# Buck_eFuse.net
KiCad netlist of a schematic drawn in EAGLE
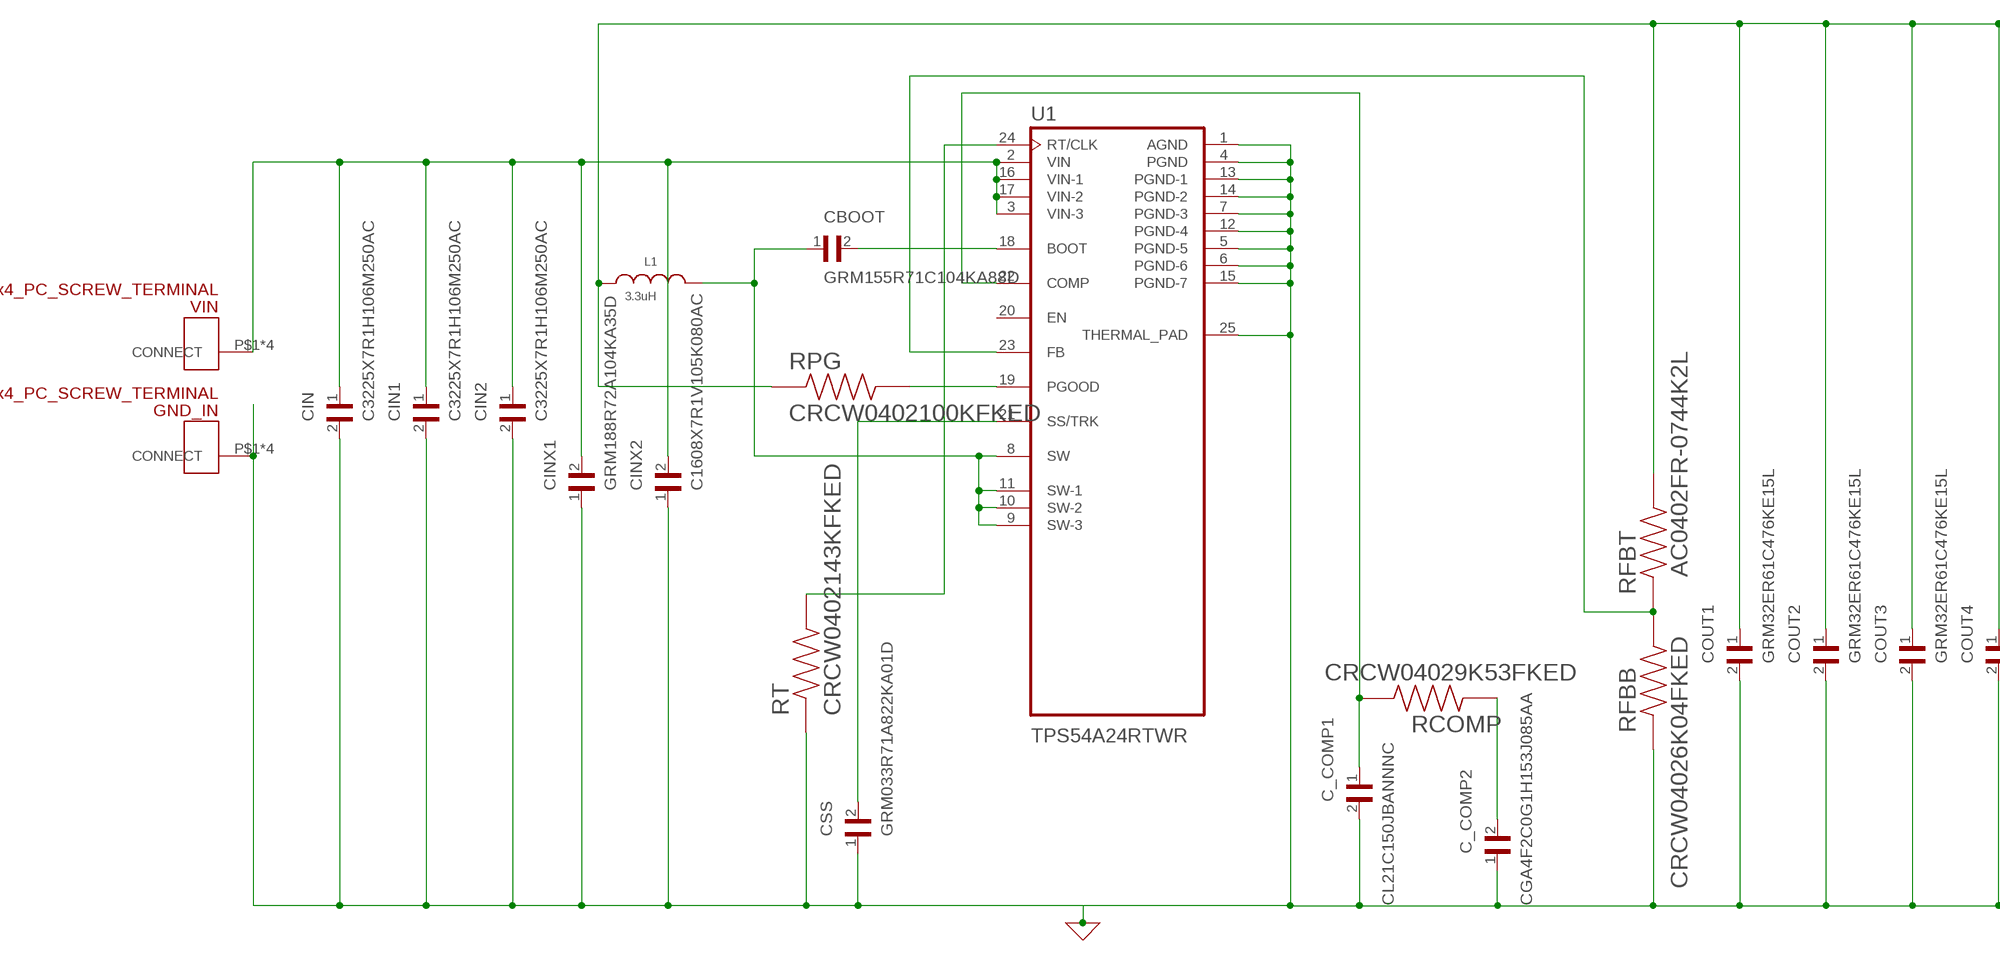
[diagram p0: schematic, sheet 1, part 1 of 2]
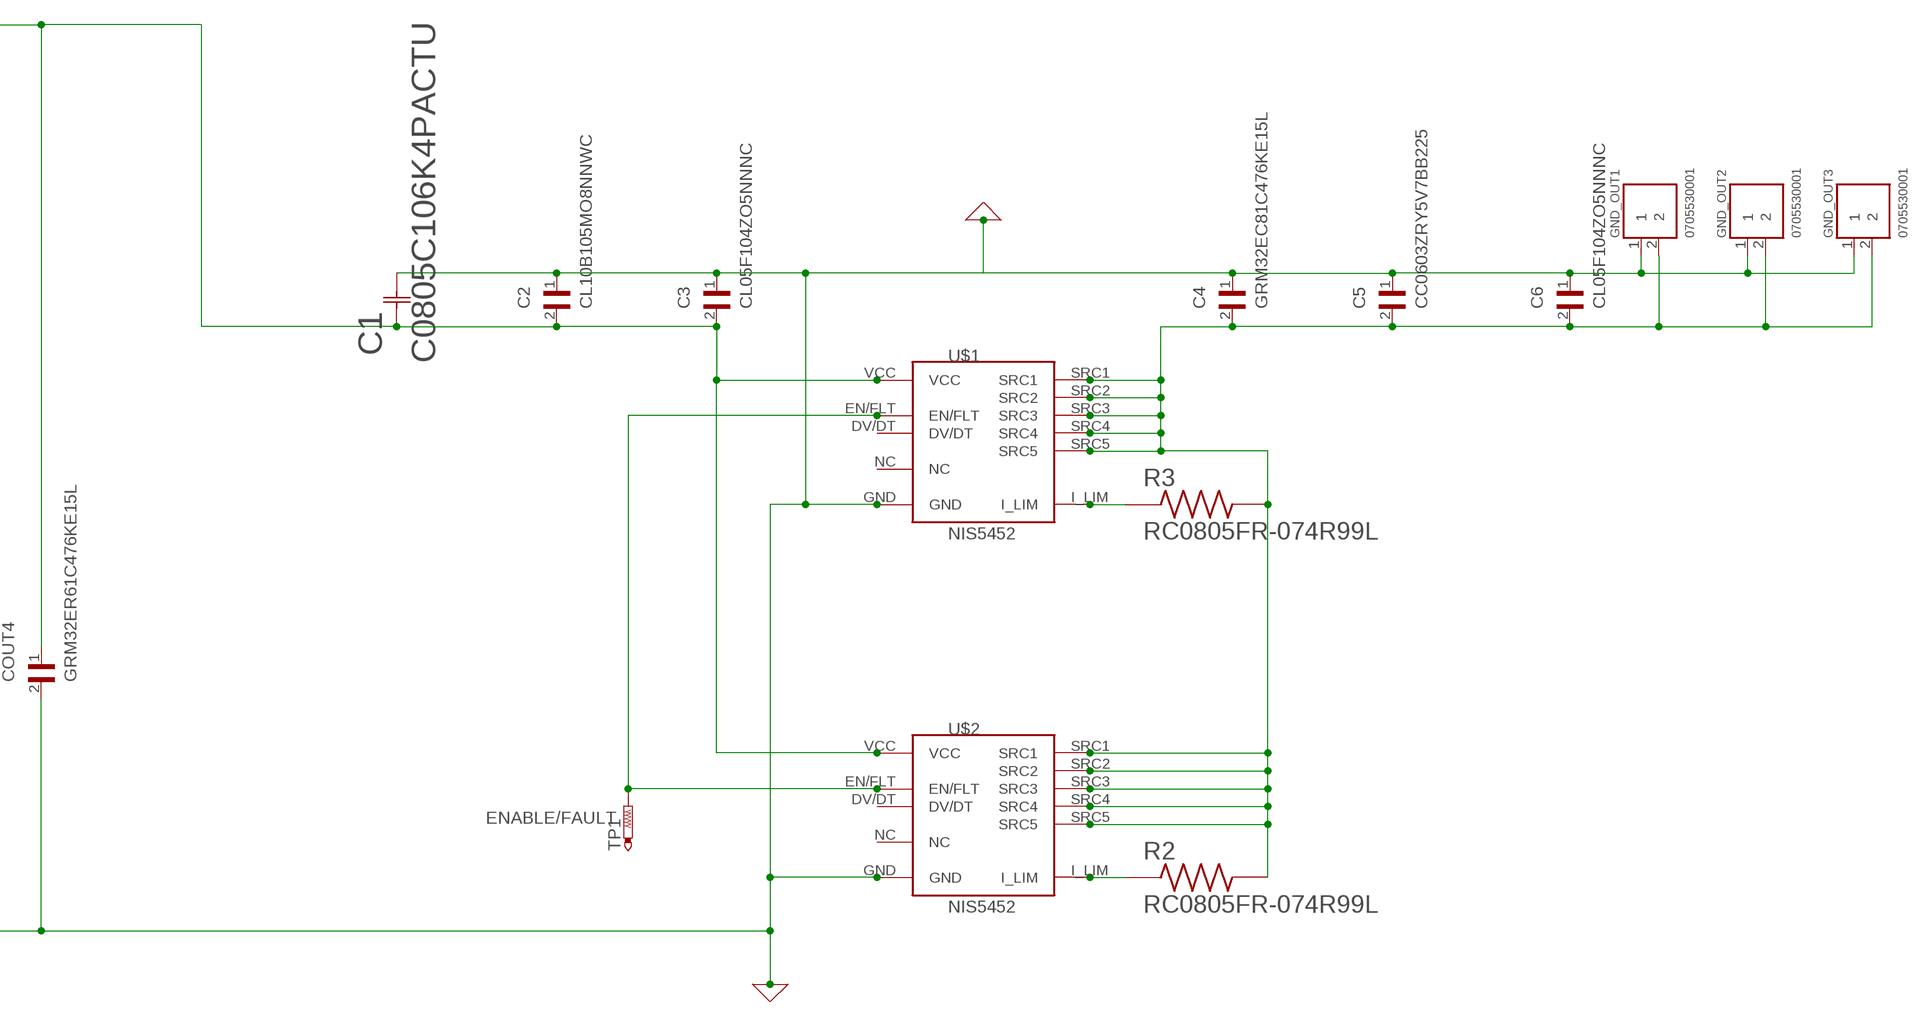
[diagram p1: schematic, sheet 1, part 2 of 2]

(export (version "E")
  (design (tool "Eeschema 10.0.6"))
  (components
    (comp (ref "C1")
      (value "C0805C106K4PACTU")
      (footprint "eagle-import:CAP_C0805")
      (libsource (lib "eagle-import") (part "C0805C106K4PACTU"))
    )
    (comp (ref "C2")
      (value "CL10B105MO8NNWC")
      (footprint "eagle-import:CAPC1608X90N")
      (fields
        (field (name "DIGI-KEY_PART_NUMBER") "1276-6524-1-ND")
        (field (name "MF") "Samsung Electro-Mechanics")
      )
      (libsource (lib "eagle-import") (part "CL10B105MO8NNWC"))
    )
    (comp (ref "C3")
      (value "CL05F104ZO5NNNC")
      (footprint "eagle-import:CAPC1005X55N")
      (fields
        (field (name "DIGI-KEY_PART_NUMBER") "1276-1004-1-ND")
        (field (name "MF") "Samsung Electro-Mechanics")
      )
      (libsource (lib "eagle-import") (part "CL05F104ZO5NNNC"))
    )
    (comp (ref "C4")
      (value "GRM32EC81C476KE15L")
      (footprint "eagle-import:CAPC3225X270N")
      (fields (field (name "DIGI-KEY_PART_NUMBER") "490-10531-1-ND") (field (name "MF") "Murata Electronics"))
      (libsource (lib "eagle-import") (part "GRM32EC81C476KE15L"))
    )
    (comp (ref "C5")
      (value "CC0603ZRY5V7BB225")
      (footprint "eagle-import:CAPC1608X90")
      (fields (field (name "DIGI-KEY_PART_NUMBER") "311-3416-1-ND") (field (name "MF") "Yageo"))
      (libsource (lib "eagle-import") (part "CC0603ZRY5V7BB225"))
    )
    (comp (ref "C6")
      (value "CL05F104ZO5NNNC")
      (footprint "eagle-import:CAPC1005X55N")
      (fields
        (field (name "DIGI-KEY_PART_NUMBER") "1276-1004-1-ND")
        (field (name "MF") "Samsung Electro-Mechanics")
      )
      (libsource (lib "eagle-import") (part "CL05F104ZO5NNNC"))
    )
    (comp (ref "CBOOT")
      (value "GRM155R71C104KA88D")
      (footprint "eagle-import:CAPC1005X55N")
      (fields (field (name "MF") "Murata"))
      (libsource (lib "eagle-import") (part "GRM155R71C104KA88D"))
    )
    (comp (ref "CIN")
      (value "C3225X7R1H106M250AC")
      (footprint "eagle-import:CAPC3225X280N")
      (fields (field (name "DIGI-KEY_PART_NUMBER") "445-14933-1-ND") (field (name "MF") "TDK"))
      (libsource (lib "eagle-import") (part "C3225X7R1H106M250AC"))
    )
    (comp (ref "CIN1")
      (value "C3225X7R1H106M250AC")
      (footprint "eagle-import:CAPC3225X280N")
      (fields (field (name "DIGI-KEY_PART_NUMBER") "445-14933-1-ND") (field (name "MF") "TDK"))
      (libsource (lib "eagle-import") (part "C3225X7R1H106M250AC"))
    )
    (comp (ref "CIN2")
      (value "C3225X7R1H106M250AC")
      (footprint "eagle-import:CAPC3225X280N")
      (fields (field (name "DIGI-KEY_PART_NUMBER") "445-14933-1-ND") (field (name "MF") "TDK"))
      (libsource (lib "eagle-import") (part "C3225X7R1H106M250AC"))
    )
    (comp (ref "CINX1")
      (value "GRM188R72A104KA35D")
      (footprint "eagle-import:CAPC1608X90N")
      (fields (field (name "MF") "Murata Electronics"))
      (libsource (lib "eagle-import") (part "GRM188R72A104KA35D"))
    )
    (comp (ref "CINX2")
      (value "C1608X7R1V105K080AC")
      (footprint "eagle-import:CAPC1608X90N")
      (fields (field (name "MF") "TDK"))
      (libsource (lib "eagle-import") (part "C1608X7R1V105K080AC"))
    )
    (comp (ref "COUT1")
      (value "GRM32ER61C476KE15L")
      (footprint "eagle-import:CAPC3225X270N")
      (fields (field (name "MF") "Murata Electronics"))
      (libsource (lib "eagle-import") (part "GRM32ER61C476KE15L"))
    )
    (comp (ref "COUT2")
      (value "GRM32ER61C476KE15L")
      (footprint "eagle-import:CAPC3225X270N")
      (fields (field (name "MF") "Murata Electronics"))
      (libsource (lib "eagle-import") (part "GRM32ER61C476KE15L"))
    )
    (comp (ref "COUT3")
      (value "GRM32ER61C476KE15L")
      (footprint "eagle-import:CAPC3225X270N")
      (fields (field (name "MF") "Murata Electronics"))
      (libsource (lib "eagle-import") (part "GRM32ER61C476KE15L"))
    )
    (comp (ref "COUT4")
      (value "GRM32ER61C476KE15L")
      (footprint "eagle-import:CAPC3225X270N")
      (fields (field (name "MF") "Murata Electronics"))
      (libsource (lib "eagle-import") (part "GRM32ER61C476KE15L"))
    )
    (comp (ref "CSS")
      (value "GRM033R71A822KA01D")
      (footprint "eagle-import:CAPC0603X33N")
      (fields (field (name "MF") "Murata Electronics"))
      (libsource (lib "eagle-import") (part "GRM033R71A822KA01D"))
    )
    (comp (ref "C_COMP1")
      (value "CL21C150JBANNNC")
      (footprint "eagle-import:CAPC2012X140N")
      (fields (field (name "MF") "Samsung"))
      (libsource (lib "eagle-import") (part "CL21C150JBANNNC"))
    )
    (comp (ref "C_COMP2")
      (value "CGA4F2C0G1H153J085AA")
      (footprint "eagle-import:CAPC2012X100N")
      (fields (field (name "MF") "TDK"))
      (libsource (lib "eagle-import") (part "CGA4F2C0G1H153J085AA"))
    )
    (comp (ref "GND_IN")
      (value "2X2_PC_SCREW_TERMINAL")
      (footprint "eagle-import:SCREW_TERMINAL")
      (libsource (lib "eagle-import") (part "2X2_PC_SCREW_TERMINAL"))
    )
    (comp (ref "GND_OUT1")
      (value "0705530001")
      (footprint "eagle-import:MOLEX_0705530001")
      (fields (field (name "DIGI-KEY_PART_NUMBER") "WM4900-ND") (field (name "MF") "Molex"))
      (libsource (lib "eagle-import") (part "0705530001"))
    )
    (comp (ref "GND_OUT2")
      (value "0705530001")
      (footprint "eagle-import:MOLEX_0705530001")
      (fields (field (name "DIGI-KEY_PART_NUMBER") "WM4900-ND") (field (name "MF") "Molex"))
      (libsource (lib "eagle-import") (part "0705530001"))
    )
    (comp (ref "GND_OUT3")
      (value "0705530001")
      (footprint "eagle-import:MOLEX_0705530001")
      (fields (field (name "DIGI-KEY_PART_NUMBER") "WM4900-ND") (field (name "MF") "Molex"))
      (libsource (lib "eagle-import") (part "0705530001"))
    )
    (comp (ref "L1")
      (value "3.3uH")
      (footprint "eagle-import:WE-HCC_1090")
      (libsource (lib "eagle-import") (part "WE-HCC_1090_7443330330"))
    )
    (comp (ref "R2")
      (value "RC0805FR-074R99L")
      (footprint "eagle-import:RESC2012X60N")
      (fields (field (name "DIGI-KEY_PART_NUMBER") "311-4.99CRCT-ND") (field (name "MF") "Yageo"))
      (libsource (lib "eagle-import") (part "RC0805FR-074R99L"))
    )
    (comp (ref "R3")
      (value "RC0805FR-074R99L")
      (footprint "eagle-import:RESC2012X60N")
      (fields (field (name "DIGI-KEY_PART_NUMBER") "311-4.99CRCT-ND") (field (name "MF") "Yageo"))
      (libsource (lib "eagle-import") (part "RC0805FR-074R99L"))
    )
    (comp (ref "RCOMP")
      (value "CRCW04029K53FKED")
      (footprint "eagle-import:RESC1005X40N")
      (fields (field (name "MF") "Vishay"))
      (libsource (lib "eagle-import") (part "CRCW04029K53FKED"))
    )
    (comp (ref "RFBB")
      (value "CRCW04026K04FKED")
      (footprint "eagle-import:RESC1005X40N")
      (fields (field (name "MF") "Vishay Dale"))
      (libsource (lib "eagle-import") (part "CRCW04026K04FKED"))
    )
    (comp (ref "RFBT")
      (value "AC0402FR-0744K2L")
      (footprint "eagle-import:RESC1005X37N")
      (fields (field (name "MF") "Yageo"))
      (libsource (lib "eagle-import") (part "AC0402FR-0744K2L"))
    )
    (comp (ref "RPG")
      (value "CRCW0402100KFKED")
      (footprint "eagle-import:RESC1005X40N")
      (fields (field (name "MF") "Vishay"))
      (libsource (lib "eagle-import") (part "CRCW0402100KFKED"))
    )
    (comp (ref "RT")
      (value "CRCW0402143KFKED")
      (footprint "eagle-import:RESC1005X40N")
      (fields (field (name "MF") "Vishay"))
      (libsource (lib "eagle-import") (part "CRCW0402143KFKED"))
    )
    (comp (ref "TP1")
      (value "PTR1B2,54")
      (footprint "eagle-import:B2,54")
      (libsource (lib "eagle-import") (part "PTR1B2,54"))
    )
    (comp (ref "U$1")
      (value "NIS5452")
      (footprint "eagle-import:WDFN10")
      (libsource (lib "eagle-import") (part "NIS5452"))
    )
    (comp (ref "U$2")
      (value "NIS5452")
      (footprint "eagle-import:WDFN10")
      (libsource (lib "eagle-import") (part "NIS5452"))
    )
    (comp (ref "U1")
      (value "TPS54A24RTWR")
      (footprint "eagle-import:VQFN50P400X400X100-24N")
      (fields (field (name "MF") "Texas Instruments"))
      (libsource (lib "eagle-import") (part "TPS54A24RTWR"))
    )
    (comp (ref "VIN")
      (value "2X2_PC_SCREW_TERMINAL")
      (footprint "eagle-import:SCREW_TERMINAL")
      (libsource (lib "eagle-import") (part "2X2_PC_SCREW_TERMINAL"))
    )
  )
  (nets
    (net (code "1") (name "/ENABLE{slash}FAULT") (class "Default")
      (node (ref "TP1") (pin "TP") (pinfunction "TP_TP") (pintype "input"))
      (node (ref "U$1") (pin "EN/FLT") (pinfunction "EN/FLT_EN/FLT") (pintype "bidirectional"))
      (node (ref "U$2") (pin "EN/FLT") (pinfunction "EN/FLT_EN/FLT") (pintype "bidirectional"))
    )
    (net (code "2") (name "GND") (class "Default")
      (node (ref "C1") (pin "2") (pinfunction "2_2") (pintype "passive"))
      (node (ref "C2") (pin "1") (pinfunction "1_1") (pintype "passive"))
      (node (ref "C3") (pin "1") (pinfunction "1_1") (pintype "passive"))
      (node (ref "C4") (pin "1") (pinfunction "1_1") (pintype "passive"))
      (node (ref "C5") (pin "1") (pinfunction "1_1") (pintype "passive"))
      (node (ref "C6") (pin "1") (pinfunction "1_1") (pintype "passive"))
      (node (ref "CIN") (pin "2") (pinfunction "2_2") (pintype "passive"))
      (node (ref "CIN1") (pin "2") (pinfunction "2_2") (pintype "passive"))
      (node (ref "CIN2") (pin "2") (pinfunction "2_2") (pintype "passive"))
      (node (ref "CINX1") (pin "1") (pinfunction "1_1") (pintype "passive"))
      (node (ref "CINX2") (pin "1") (pinfunction "1_1") (pintype "passive"))
      (node (ref "COUT1") (pin "2") (pinfunction "2_2") (pintype "passive"))
      (node (ref "COUT2") (pin "2") (pinfunction "2_2") (pintype "passive"))
      (node (ref "COUT3") (pin "2") (pinfunction "2_2") (pintype "passive"))
      (node (ref "COUT4") (pin "2") (pinfunction "2_2") (pintype "passive"))
      (node (ref "CSS") (pin "1") (pinfunction "1_1") (pintype "passive"))
      (node (ref "C_COMP1") (pin "2") (pinfunction "2_2") (pintype "passive"))
      (node (ref "C_COMP2") (pin "1") (pinfunction "1_1") (pintype "passive"))
      (node (ref "GND_IN") (pin "P$1") (pinfunction "CONNECT_P$1") (pintype "bidirectional"))
      (node (ref "GND_IN") (pin "P$2") (pinfunction "CONNECT_P$2") (pintype "bidirectional"))
      (node (ref "GND_IN") (pin "P$3") (pinfunction "CONNECT_P$3") (pintype "bidirectional"))
      (node (ref "GND_IN") (pin "P$4") (pinfunction "CONNECT_P$4") (pintype "bidirectional"))
      (node (ref "GND_OUT1") (pin "1") (pinfunction "1_1") (pintype "passive"))
      (node (ref "GND_OUT2") (pin "1") (pinfunction "1_1") (pintype "passive"))
      (node (ref "GND_OUT3") (pin "1") (pinfunction "1_1") (pintype "passive"))
      (node (ref "RFBB") (pin "1") (pinfunction "1_1") (pintype "passive"))
      (node (ref "RT") (pin "1") (pinfunction "1_1") (pintype "passive"))
      (node (ref "U$1") (pin "GND") (pinfunction "GND_GND") (pintype "power_in"))
      (node (ref "U$2") (pin "GND") (pinfunction "GND_GND") (pintype "power_in"))
      (node (ref "U1") (pin "1") (pinfunction "AGND_1") (pintype "power_in"))
      (node (ref "U1") (pin "12") (pinfunction "PGND-4_12") (pintype "power_in"))
      (node (ref "U1") (pin "13") (pinfunction "PGND-1_13") (pintype "power_in"))
      (node (ref "U1") (pin "14") (pinfunction "PGND-2_14") (pintype "power_in"))
      (node (ref "U1") (pin "15") (pinfunction "PGND-7_15") (pintype "power_in"))
      (node (ref "U1") (pin "25") (pinfunction "THERMAL_PAD_25") (pintype "bidirectional"))
      (node (ref "U1") (pin "4") (pinfunction "PGND_4") (pintype "power_in"))
      (node (ref "U1") (pin "5") (pinfunction "PGND-5_5") (pintype "power_in"))
      (node (ref "U1") (pin "6") (pinfunction "PGND-6_6") (pintype "power_in"))
      (node (ref "U1") (pin "7") (pinfunction "PGND-3_7") (pintype "power_in"))
    )
    (net (code "3") (name "Net-(C1-Pad1)") (class "Default")
      (node (ref "C1") (pin "1") (pinfunction "1_1") (pintype "passive"))
      (node (ref "C2") (pin "2") (pinfunction "2_2") (pintype "passive"))
      (node (ref "C3") (pin "2") (pinfunction "2_2") (pintype "passive"))
      (node (ref "COUT1") (pin "1") (pinfunction "1_1") (pintype "passive"))
      (node (ref "COUT2") (pin "1") (pinfunction "1_1") (pintype "passive"))
      (node (ref "COUT3") (pin "1") (pinfunction "1_1") (pintype "passive"))
      (node (ref "COUT4") (pin "1") (pinfunction "1_1") (pintype "passive"))
      (node (ref "L1") (pin "1") (pinfunction "1_1") (pintype "passive"))
      (node (ref "RFBT") (pin "2") (pinfunction "2_2") (pintype "passive"))
      (node (ref "RPG") (pin "1") (pinfunction "1_1") (pintype "passive"))
      (node (ref "U$1") (pin "VCC") (pinfunction "VCC_VCC") (pintype "power_in"))
      (node (ref "U$2") (pin "VCC") (pinfunction "VCC_VCC") (pintype "power_in"))
    )
    (net (code "4") (name "Net-(C4-Pad2)") (class "Default")
      (node (ref "C4") (pin "2") (pinfunction "2_2") (pintype "passive"))
      (node (ref "C5") (pin "2") (pinfunction "2_2") (pintype "passive"))
      (node (ref "C6") (pin "2") (pinfunction "2_2") (pintype "passive"))
      (node (ref "GND_OUT1") (pin "2") (pinfunction "2_2") (pintype "passive"))
      (node (ref "GND_OUT2") (pin "2") (pinfunction "2_2") (pintype "passive"))
      (node (ref "GND_OUT3") (pin "2") (pinfunction "2_2") (pintype "passive"))
      (node (ref "R2") (pin "2") (pinfunction "2_2") (pintype "passive"))
      (node (ref "R3") (pin "2") (pinfunction "2_2") (pintype "passive"))
      (node (ref "U$1") (pin "SRC1") (pinfunction "SRC1_SRC1") (pintype "output"))
      (node (ref "U$1") (pin "SRC2") (pinfunction "SRC2_SRC2") (pintype "output"))
      (node (ref "U$1") (pin "SRC3") (pinfunction "SRC3_SRC3") (pintype "output"))
      (node (ref "U$1") (pin "SRC4") (pinfunction "SRC4_SRC4") (pintype "output"))
      (node (ref "U$1") (pin "SRC5") (pinfunction "SRC5_SRC5") (pintype "output"))
      (node (ref "U$2") (pin "SRC1") (pinfunction "SRC1_SRC1") (pintype "output"))
      (node (ref "U$2") (pin "SRC2") (pinfunction "SRC2_SRC2") (pintype "output"))
      (node (ref "U$2") (pin "SRC3") (pinfunction "SRC3_SRC3") (pintype "output"))
      (node (ref "U$2") (pin "SRC4") (pinfunction "SRC4_SRC4") (pintype "output"))
      (node (ref "U$2") (pin "SRC5") (pinfunction "SRC5_SRC5") (pintype "output"))
    )
    (net (code "5") (name "Net-(C_COMP2-Pad2)") (class "Default")
      (node (ref "C_COMP2") (pin "2") (pinfunction "2_2") (pintype "passive"))
      (node (ref "RCOMP") (pin "2") (pinfunction "2_2") (pintype "passive"))
    )
    (net (code "6") (name "Net-(R2-Pad1)") (class "Default")
      (node (ref "R2") (pin "1") (pinfunction "1_1") (pintype "passive"))
      (node (ref "U$2") (pin "I_LIM") (pinfunction "I_LIM_I_LIM") (pintype "bidirectional"))
    )
    (net (code "7") (name "Net-(R3-Pad1)") (class "Default")
      (node (ref "R3") (pin "1") (pinfunction "1_1") (pintype "passive"))
      (node (ref "U$1") (pin "I_LIM") (pinfunction "I_LIM_I_LIM") (pintype "bidirectional"))
    )
    (net (code "8") (name "Net-(U1-BOOT)") (class "Default")
      (node (ref "CBOOT") (pin "2") (pinfunction "2_2") (pintype "passive"))
      (node (ref "U1") (pin "18") (pinfunction "BOOT_18") (pintype "bidirectional"))
    )
    (net (code "9") (name "Net-(U1-COMP)") (class "Default")
      (node (ref "C_COMP1") (pin "1") (pinfunction "1_1") (pintype "passive"))
      (node (ref "RCOMP") (pin "1") (pinfunction "1_1") (pintype "passive"))
      (node (ref "U1") (pin "22") (pinfunction "COMP_22") (pintype "bidirectional"))
    )
    (net (code "10") (name "Net-(U1-FB)") (class "Default")
      (node (ref "RFBB") (pin "2") (pinfunction "2_2") (pintype "passive"))
      (node (ref "RFBT") (pin "1") (pinfunction "1_1") (pintype "passive"))
      (node (ref "U1") (pin "23") (pinfunction "FB_23") (pintype "bidirectional"))
    )
    (net (code "11") (name "Net-(U1-PGOOD)") (class "Default")
      (node (ref "RPG") (pin "2") (pinfunction "2_2") (pintype "passive"))
      (node (ref "U1") (pin "19") (pinfunction "PGOOD_19") (pintype "bidirectional"))
    )
    (net (code "12") (name "Net-(U1-RT{slash}CLK)") (class "Default")
      (node (ref "RT") (pin "2") (pinfunction "2_2") (pintype "passive"))
      (node (ref "U1") (pin "24") (pinfunction "RT/CLK_24") (pintype "input"))
    )
    (net (code "13") (name "Net-(U1-SS{slash}TRK)") (class "Default")
      (node (ref "CSS") (pin "2") (pinfunction "2_2") (pintype "passive"))
      (node (ref "U1") (pin "21") (pinfunction "SS/TRK_21") (pintype "bidirectional"))
    )
    (net (code "14") (name "Net-(U1-SW)") (class "Default")
      (node (ref "CBOOT") (pin "1") (pinfunction "1_1") (pintype "passive"))
      (node (ref "L1") (pin "2") (pinfunction "2_2") (pintype "passive"))
      (node (ref "U1") (pin "10") (pinfunction "SW-2_10") (pintype "bidirectional"))
      (node (ref "U1") (pin "11") (pinfunction "SW-1_11") (pintype "bidirectional"))
      (node (ref "U1") (pin "8") (pinfunction "SW_8") (pintype "bidirectional"))
      (node (ref "U1") (pin "9") (pinfunction "SW-3_9") (pintype "bidirectional"))
    )
    (net (code "15") (name "Net-(U1-VIN)") (class "Default")
      (node (ref "CIN") (pin "1") (pinfunction "1_1") (pintype "passive"))
      (node (ref "CIN1") (pin "1") (pinfunction "1_1") (pintype "passive"))
      (node (ref "CIN2") (pin "1") (pinfunction "1_1") (pintype "passive"))
      (node (ref "CINX1") (pin "2") (pinfunction "2_2") (pintype "passive"))
      (node (ref "CINX2") (pin "2") (pinfunction "2_2") (pintype "passive"))
      (node (ref "U1") (pin "16") (pinfunction "VIN-1_16") (pintype "input"))
      (node (ref "U1") (pin "17") (pinfunction "VIN-2_17") (pintype "input"))
      (node (ref "U1") (pin "2") (pinfunction "VIN_2") (pintype "input"))
      (node (ref "U1") (pin "3") (pinfunction "VIN-3_3") (pintype "input"))
      (node (ref "VIN") (pin "P$1") (pinfunction "CONNECT_P$1") (pintype "bidirectional"))
      (node (ref "VIN") (pin "P$2") (pinfunction "CONNECT_P$2") (pintype "bidirectional"))
      (node (ref "VIN") (pin "P$3") (pinfunction "CONNECT_P$3") (pintype "bidirectional"))
      (node (ref "VIN") (pin "P$4") (pinfunction "CONNECT_P$4") (pintype "bidirectional"))
    )
    (net (code "16") (name "unconnected-(U$1-PadDV{slash}DT)") (class "Default")
      (node (ref "U$1") (pin "DV/DT") (pinfunction "DV/DT_DV/DT") (pintype "bidirectional"))
    )
    (net (code "17") (name "unconnected-(U$1-PadNC)") (class "Default")
      (node (ref "U$1") (pin "NC") (pinfunction "NC_NC") (pintype "no_connect"))
    )
    (net (code "18") (name "unconnected-(U$2-PadDV{slash}DT)") (class "Default")
      (node (ref "U$2") (pin "DV/DT") (pinfunction "DV/DT_DV/DT") (pintype "bidirectional"))
    )
    (net (code "19") (name "unconnected-(U$2-PadNC)") (class "Default")
      (node (ref "U$2") (pin "NC") (pinfunction "NC_NC") (pintype "no_connect"))
    )
    (net (code "20") (name "unconnected-(U1-EN-Pad20)") (class "Default")
      (node (ref "U1") (pin "20") (pinfunction "EN_20") (pintype "bidirectional"))
    )
  )
)
